# AVR.net
KiCad netlist of a schematic drawn in Altium Designer
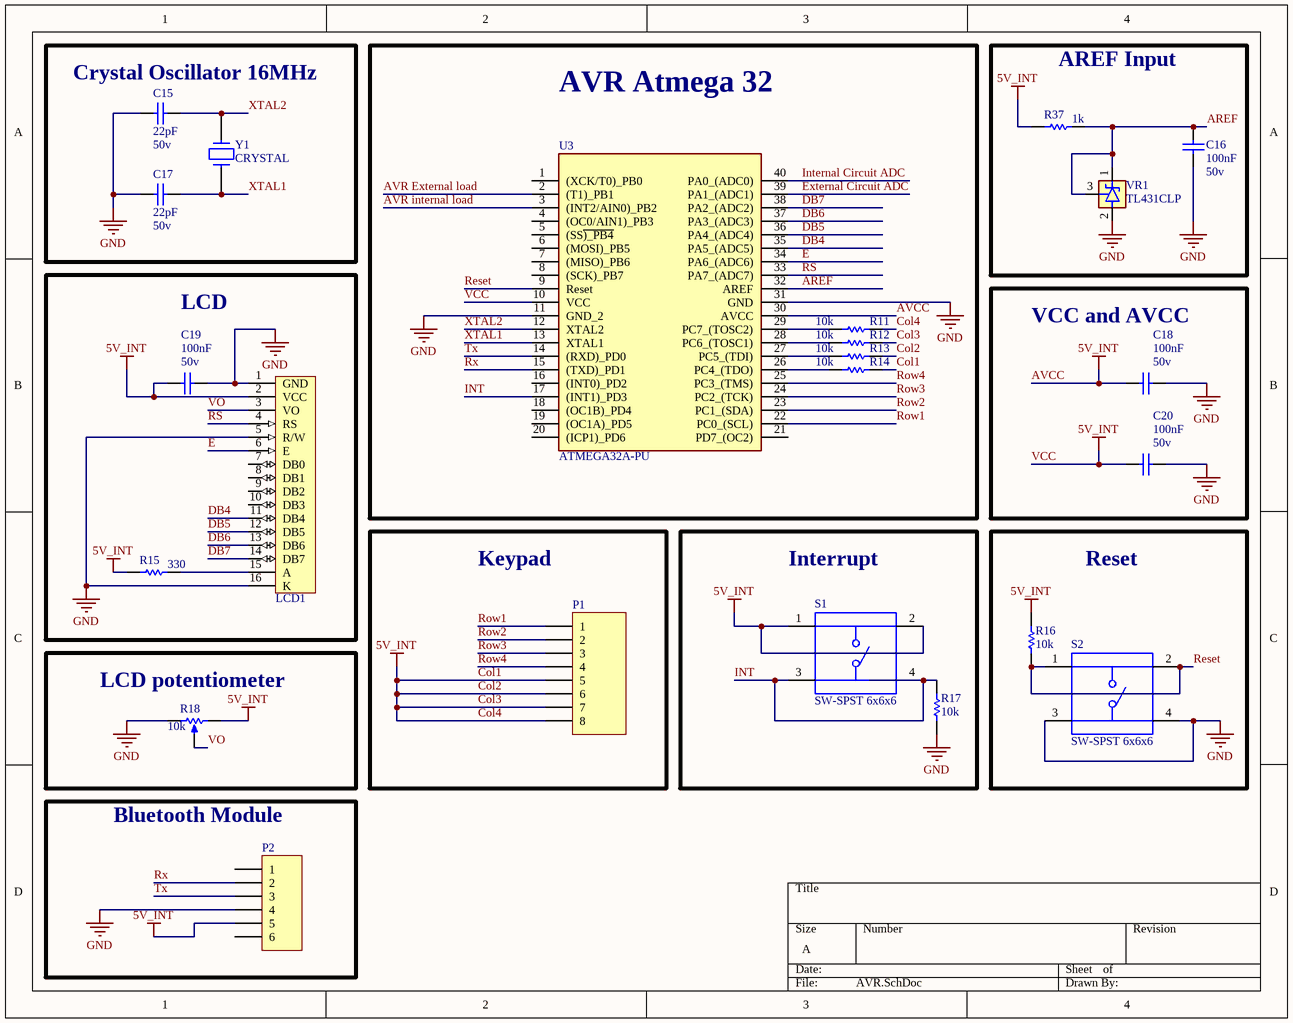
[diagram p0: AVR.SchDoc]

(export (version "E")
  (design (tool "Eeschema 10.0.6"))
  (components
    (comp (ref "C15")
      (value "22pF")
      (footprint "C0805")
      (description "None polar capacitor")
      (fields (field (name "ASID PART NUMBER") "C-AS") (field (name "VOLTE") "50v"))
      (libsource (lib "Mylib+Rev+4") (part "Cap ceramic"))
    )
    (comp (ref "C16")
      (value "100nF")
      (footprint "C0805")
      (description "None polar capacitor")
      (fields (field (name "ASID PART NUMBER") "C-AS") (field (name "VOLTE") "50v"))
      (libsource (lib "Mylib+Rev+4") (part "Cap ceramic"))
    )
    (comp (ref "C17")
      (value "22pF")
      (footprint "C0805")
      (description "None polar capacitor")
      (fields (field (name "ASID PART NUMBER") "C-AS") (field (name "VOLTE") "50v"))
      (libsource (lib "Mylib+Rev+4") (part "Cap ceramic"))
    )
    (comp (ref "C18")
      (value "100nF")
      (footprint "C0805")
      (description "None polar capacitor")
      (fields (field (name "ASID PART NUMBER") "C-AS") (field (name "VOLTE") "50v"))
      (libsource (lib "Mylib+Rev+4") (part "Cap ceramic"))
    )
    (comp (ref "C19")
      (value "100nF")
      (footprint "C0805")
      (description "None polar capacitor")
      (fields (field (name "ASID PART NUMBER") "C-AS") (field (name "VOLTE") "50v"))
      (libsource (lib "Mylib+Rev+4") (part "Cap ceramic"))
    )
    (comp (ref "C20")
      (value "100nF")
      (footprint "C0805")
      (description "None polar capacitor")
      (fields (field (name "ASID PART NUMBER") "C-AS") (field (name "VOLTE") "50v"))
      (libsource (lib "Mylib+Rev+4") (part "Cap ceramic"))
    )
    (comp (ref "LCD1")
      (value "LCD 16X2")
      (footprint "My_LCD 16x2-A")
      (description "LCD 16X2 Character lcd")
      (fields (field (name "ASID PART NUMBER") "LCD 16X2-AS"))
      (libsource (lib "Mylib+Rev+4") (part "LCD 16X2"))
    )
    (comp (ref "P1")
      (value "Header 8")
      (footprint "MY_1X08")
      (description "Header, 8-Pin, Dual row")
      (fields (field (name "ASID PART NUMBER") "Header 8-AS"))
      (libsource (lib "Mylib+Rev+4") (part "Header 8"))
    )
    (comp (ref "P2")
      (value "Header 6")
      (footprint "MY_FE06")
      (description "Header, 6-Pin")
      (fields (field (name "ASID PART NUMBER") "Header 6-AS"))
      (libsource (lib "Mylib+Rev+4") (part "Header 6"))
    )
    (comp (ref "R11")
      (value "10k")
      (footprint "R0603")
      (description "Standard resistor")
      (fields (field (name "ASID PART NUMBER") "Res-AS"))
      (libsource (lib "Mylib+Rev+4") (part "Res"))
    )
    (comp (ref "R12")
      (value "10k")
      (footprint "R0603")
      (description "Standard resistor")
      (fields (field (name "ASID PART NUMBER") "Res-AS"))
      (libsource (lib "Mylib+Rev+4") (part "Res"))
    )
    (comp (ref "R13")
      (value "10k")
      (footprint "R0603")
      (description "Standard resistor")
      (fields (field (name "ASID PART NUMBER") "Res-AS"))
      (libsource (lib "Mylib+Rev+4") (part "Res"))
    )
    (comp (ref "R14")
      (value "10k")
      (footprint "R0603")
      (description "Standard resistor")
      (fields (field (name "ASID PART NUMBER") "Res-AS"))
      (libsource (lib "Mylib+Rev+4") (part "Res"))
    )
    (comp (ref "R15")
      (value "330")
      (footprint "MY_(0.25w)_0207_10")
      (description "Standard resistor")
      (fields (field (name "ASID PART NUMBER") "Res-AS"))
      (libsource (lib "Mylib+Rev+4") (part "Res"))
    )
    (comp (ref "R16")
      (value "10k")
      (footprint "R0603")
      (description "Standard resistor")
      (fields (field (name "ASID PART NUMBER") "Res-AS"))
      (libsource (lib "Mylib+Rev+4") (part "Res"))
    )
    (comp (ref "R17")
      (value "10k")
      (footprint "R0603")
      (description "Standard resistor")
      (fields (field (name "ASID PART NUMBER") "Res-AS"))
      (libsource (lib "Mylib+Rev+4") (part "Res"))
    )
    (comp (ref "R18")
      (value "10k")
      (footprint "MY_TRIM3296W")
      (description "Potentiometer")
      (fields (field (name "ASID PART NUMBER") "Variable Resistor-AS"))
      (libsource (lib "Mylib+Rev+4") (part "Variable Resistor"))
    )
    (comp (ref "R37")
      (value "1k")
      (footprint "R0603")
      (description "Standard resistor")
      (fields (field (name "ASID PART NUMBER") "Res-AS"))
      (libsource (lib "Mylib+Rev+4") (part "Res"))
    )
    (comp (ref "S1")
      (value "SW-SPST 6x6x6")
      (footprint "SW-SPST 6x6x6")
      (description "6 x 6 mm, 6 mm Actuator Height, 160 gf, Black, Long Crimped, Through Hole, SPST, Tactile Switch")
      (fields (field (name "MF") "CUI Devices") (field (name "MP") "TS02-66-60-BK-160-LCR-D"))
      (libsource (lib "Miscellaneous Devices") (part "SW-SPST 6x6x6"))
    )
    (comp (ref "S2")
      (value "SW-SPST 6x6x6")
      (footprint "SW-SPST 6x6x6")
      (description "6 x 6 mm, 6 mm Actuator Height, 160 gf, Black, Long Crimped, Through Hole, SPST, Tactile Switch")
      (fields (field (name "MF") "CUI Devices") (field (name "MP") "TS02-66-60-BK-160-LCR-D"))
      (libsource (lib "Miscellaneous Devices") (part "SW-SPST 6x6x6"))
    )
    (comp (ref "U3")
      (value "ATMEGA32A-PU")
      (footprint "DIP40")
      (description "AVR AVR ATmega Microcontroller IC 8-Bit 16MHz 32KB (16K x 16) FLASH 40-PDIP")
      (fields (field (name "MF") "Microchip"))
      (libsource (lib "Mylib+Rev+4") (part "ATMEGA32A-PU"))
    )
    (comp (ref "VR1")
      (value "TL431CLP")
      (footprint "TO-92")
      (description "Adjustable precision shunt regulator")
      (fields (field (name "MF") "Texas Instruments"))
      (libsource (lib "Mylib+Rev+4") (part "TL431CLP"))
    )
    (comp (ref "Y1")
      (value "CRYSTAL")
      (footprint "My_Crystal")
      (description "Crystal")
      (fields (field (name "ASID PART NUMBER") "Crystal-AS"))
      (libsource (lib "Mylib+Rev+4") (part "CRYSTAL"))
    )
  )
  (nets
    (net (code "1") (name "/AREF") (class "Default")
      (node (ref "C16") (pin "1") (pinfunction "1_1") (pintype "passive"))
      (node (ref "R37") (pin "2") (pinfunction "2_2") (pintype "passive"))
      (node (ref "U3") (pin "32") (pinfunction "AREF_32") (pintype "passive"))
      (node (ref "VR1") (pin "1") (pinfunction "CATHODE_1") (pintype "passive"))
      (node (ref "VR1") (pin "3") (pinfunction "REF_3") (pintype "passive"))
    )
    (net (code "2") (name "/AVR External load") (class "Default")
      (node (ref "U3") (pin "2") (pinfunction "(T1)_PB1_2") (pintype "passive"))
    )
    (net (code "3") (name "/AVR internal load") (class "Default")
      (node (ref "U3") (pin "3") (pinfunction "(INT2/AIN0)_PB2_3") (pintype "passive"))
    )
    (net (code "4") (name "/DB4") (class "Default")
      (node (ref "LCD1") (pin "11") (pinfunction "DB4_11") (pintype "bidirectional"))
      (node (ref "U3") (pin "35") (pinfunction "PA5_(ADC5)_35") (pintype "passive"))
    )
    (net (code "5") (name "/DB5") (class "Default")
      (node (ref "LCD1") (pin "12") (pinfunction "DB5_12") (pintype "bidirectional"))
      (node (ref "U3") (pin "36") (pinfunction "PA4_(ADC4)_36") (pintype "passive"))
    )
    (net (code "6") (name "/DB6") (class "Default")
      (node (ref "LCD1") (pin "13") (pinfunction "DB6_13") (pintype "bidirectional"))
      (node (ref "U3") (pin "37") (pinfunction "PA3_(ADC3)_37") (pintype "passive"))
    )
    (net (code "7") (name "/DB7") (class "Default")
      (node (ref "LCD1") (pin "14") (pinfunction "DB7_14") (pintype "bidirectional"))
      (node (ref "U3") (pin "38") (pinfunction "PA2_(ADC2)_38") (pintype "passive"))
    )
    (net (code "8") (name "/E") (class "Default")
      (node (ref "LCD1") (pin "6") (pinfunction "E_6") (pintype "input"))
      (node (ref "U3") (pin "34") (pinfunction "PA6_(ADC6)_34") (pintype "passive"))
    )
    (net (code "9") (name "/External Circuit ADC") (class "Default")
      (node (ref "U3") (pin "39") (pinfunction "PA1_(ADC1)_39") (pintype "passive"))
    )
    (net (code "10") (name "/INT") (class "Default")
      (node (ref "R17") (pin "1") (pinfunction "1_1") (pintype "passive"))
      (node (ref "S1") (pin "3") (pinfunction "3_3") (pintype "passive"))
      (node (ref "S1") (pin "4") (pinfunction "4_4") (pintype "passive"))
      (node (ref "U3") (pin "17") (pinfunction "(INT1)_PD3_17") (pintype "passive"))
    )
    (net (code "11") (name "/Internal Circuit ADC") (class "Default")
      (node (ref "U3") (pin "40") (pinfunction "PA0_(ADC0)_40") (pintype "passive"))
    )
    (net (code "12") (name "/RS") (class "Default")
      (node (ref "LCD1") (pin "4") (pinfunction "RS_4") (pintype "input"))
      (node (ref "U3") (pin "33") (pinfunction "PA7_(ADC7)_33") (pintype "passive"))
    )
    (net (code "13") (name "/Reset") (class "Default")
      (node (ref "R16") (pin "2") (pinfunction "2_2") (pintype "passive"))
      (node (ref "S2") (pin "1") (pinfunction "1_1") (pintype "passive"))
      (node (ref "S2") (pin "2") (pinfunction "2_2") (pintype "passive"))
      (node (ref "U3") (pin "9") (pinfunction "Reset_9") (pintype "passive"))
    )
    (net (code "14") (name "/Row1") (class "Default")
      (node (ref "P1") (pin "1") (pinfunction "1_1") (pintype "passive"))
      (node (ref "U3") (pin "22") (pinfunction "PC0_(SCL)_22") (pintype "passive"))
    )
    (net (code "15") (name "/Row2") (class "Default")
      (node (ref "P1") (pin "2") (pinfunction "2_2") (pintype "passive"))
      (node (ref "U3") (pin "23") (pinfunction "PC1_(SDA)_23") (pintype "passive"))
    )
    (net (code "16") (name "/Row3") (class "Default")
      (node (ref "P1") (pin "3") (pinfunction "3_3") (pintype "passive"))
      (node (ref "U3") (pin "24") (pinfunction "PC2_(TCK)_24") (pintype "passive"))
    )
    (net (code "17") (name "/Row4") (class "Default")
      (node (ref "P1") (pin "4") (pinfunction "4_4") (pintype "passive"))
      (node (ref "U3") (pin "25") (pinfunction "PC3_(TMS)_25") (pintype "passive"))
    )
    (net (code "18") (name "/Rx") (class "Default")
      (node (ref "P2") (pin "2") (pinfunction "2_2") (pintype "passive"))
      (node (ref "U3") (pin "15") (pinfunction "(TXD)_PD1_15") (pintype "passive"))
    )
    (net (code "19") (name "/Tx") (class "Default")
      (node (ref "P2") (pin "3") (pinfunction "3_3") (pintype "passive"))
      (node (ref "U3") (pin "14") (pinfunction "(RXD)_PD0_14") (pintype "passive"))
    )
    (net (code "20") (name "/VO") (class "Default")
      (node (ref "LCD1") (pin "3") (pinfunction "VO_3") (pintype "passive"))
      (node (ref "R18") (pin "3") (pinfunction "TAP_3") (pintype "passive"))
    )
    (net (code "21") (name "/XTAL1") (class "Default")
      (node (ref "C17") (pin "2") (pinfunction "2_2") (pintype "passive"))
      (node (ref "U3") (pin "13") (pinfunction "XTAL1_13") (pintype "passive"))
      (node (ref "Y1") (pin "1") (pinfunction "1_1") (pintype "passive"))
    )
    (net (code "22") (name "/XTAL2") (class "Default")
      (node (ref "C15") (pin "2") (pinfunction "2_2") (pintype "passive"))
      (node (ref "U3") (pin "12") (pinfunction "XTAL2_12") (pintype "passive"))
      (node (ref "Y1") (pin "2") (pinfunction "2_2") (pintype "passive"))
    )
    (net (code "23") (name "5V_INT") (class "Default")
      (node (ref "C18") (pin "2") (pinfunction "2_2") (pintype "passive"))
      (node (ref "C19") (pin "2") (pinfunction "2_2") (pintype "passive"))
      (node (ref "C20") (pin "2") (pinfunction "2_2") (pintype "passive"))
      (node (ref "LCD1") (pin "2") (pinfunction "VCC_2") (pintype "power_in"))
      (node (ref "P1") (pin "5") (pinfunction "5_5") (pintype "passive"))
      (node (ref "P1") (pin "6") (pinfunction "6_6") (pintype "passive"))
      (node (ref "P1") (pin "7") (pinfunction "7_7") (pintype "passive"))
      (node (ref "P1") (pin "8") (pinfunction "8_8") (pintype "passive"))
      (node (ref "P2") (pin "5") (pinfunction "5_5") (pintype "passive"))
      (node (ref "R11") (pin "2") (pinfunction "2_2") (pintype "passive"))
      (node (ref "R12") (pin "2") (pinfunction "2_2") (pintype "passive"))
      (node (ref "R13") (pin "2") (pinfunction "2_2") (pintype "passive"))
      (node (ref "R14") (pin "2") (pinfunction "2_2") (pintype "passive"))
      (node (ref "R15") (pin "1") (pinfunction "1_1") (pintype "passive"))
      (node (ref "R16") (pin "1") (pinfunction "1_1") (pintype "passive"))
      (node (ref "R18") (pin "2") (pinfunction "BOT_2") (pintype "passive"))
      (node (ref "R37") (pin "1") (pinfunction "1_1") (pintype "passive"))
      (node (ref "S1") (pin "1") (pinfunction "1_1") (pintype "passive"))
      (node (ref "S1") (pin "2") (pinfunction "2_2") (pintype "passive"))
      (node (ref "U3") (pin "10") (pinfunction "VCC_10") (pintype "passive"))
      (node (ref "U3") (pin "30") (pinfunction "AVCC_30") (pintype "passive"))
    )
    (net (code "24") (name "GND") (class "Default")
      (node (ref "C15") (pin "1") (pinfunction "1_1") (pintype "passive"))
      (node (ref "C16") (pin "2") (pinfunction "2_2") (pintype "passive"))
      (node (ref "C17") (pin "1") (pinfunction "1_1") (pintype "passive"))
      (node (ref "C18") (pin "1") (pinfunction "1_1") (pintype "passive"))
      (node (ref "C19") (pin "1") (pinfunction "1_1") (pintype "passive"))
      (node (ref "C20") (pin "1") (pinfunction "1_1") (pintype "passive"))
      (node (ref "LCD1") (pin "1") (pinfunction "GND_1") (pintype "power_in"))
      (node (ref "LCD1") (pin "16") (pinfunction "K_16") (pintype "passive"))
      (node (ref "LCD1") (pin "5") (pinfunction "R/W_5") (pintype "input"))
      (node (ref "P2") (pin "4") (pinfunction "4_4") (pintype "passive"))
      (node (ref "R17") (pin "2") (pinfunction "2_2") (pintype "passive"))
      (node (ref "R18") (pin "1") (pinfunction "TOP_1") (pintype "passive"))
      (node (ref "S2") (pin "3") (pinfunction "3_3") (pintype "passive"))
      (node (ref "S2") (pin "4") (pinfunction "4_4") (pintype "passive"))
      (node (ref "U3") (pin "11") (pinfunction "GND_2_11") (pintype "passive"))
      (node (ref "U3") (pin "31") (pinfunction "GND_31") (pintype "passive"))
      (node (ref "VR1") (pin "2") (pinfunction "ANODE_2") (pintype "passive"))
    )
    (net (code "25") (name "Net-(LCD1-A)") (class "Default")
      (node (ref "LCD1") (pin "15") (pinfunction "A_15") (pintype "passive"))
      (node (ref "R15") (pin "2") (pinfunction "2_2") (pintype "passive"))
    )
    (net (code "26") (name "Net-(U3-PC4_(TDO))") (class "Default")
      (node (ref "R14") (pin "1") (pinfunction "1_1") (pintype "passive"))
      (node (ref "U3") (pin "26") (pinfunction "PC4_(TDO)_26") (pintype "passive"))
    )
    (net (code "27") (name "Net-(U3-PC5_(TDI))") (class "Default")
      (node (ref "R13") (pin "1") (pinfunction "1_1") (pintype "passive"))
      (node (ref "U3") (pin "27") (pinfunction "PC5_(TDI)_27") (pintype "passive"))
    )
    (net (code "28") (name "Net-(U3-PC6_(TOSC1))") (class "Default")
      (node (ref "R12") (pin "1") (pinfunction "1_1") (pintype "passive"))
      (node (ref "U3") (pin "28") (pinfunction "PC6_(TOSC1)_28") (pintype "passive"))
    )
    (net (code "29") (name "Net-(U3-PC7_(TOSC2))") (class "Default")
      (node (ref "R11") (pin "1") (pinfunction "1_1") (pintype "passive"))
      (node (ref "U3") (pin "29") (pinfunction "PC7_(TOSC2)_29") (pintype "passive"))
    )
    (net (code "30") (name "unconnected-(LCD1-DB0-Pad7)") (class "Default")
      (node (ref "LCD1") (pin "7") (pinfunction "DB0_7") (pintype "bidirectional"))
    )
    (net (code "31") (name "unconnected-(LCD1-DB1-Pad8)") (class "Default")
      (node (ref "LCD1") (pin "8") (pinfunction "DB1_8") (pintype "bidirectional"))
    )
    (net (code "32") (name "unconnected-(LCD1-DB2-Pad9)") (class "Default")
      (node (ref "LCD1") (pin "9") (pinfunction "DB2_9") (pintype "bidirectional"))
    )
    (net (code "33") (name "unconnected-(LCD1-DB3-Pad10)") (class "Default")
      (node (ref "LCD1") (pin "10") (pinfunction "DB3_10") (pintype "bidirectional"))
    )
    (net (code "34") (name "unconnected-(P2-Pad1)") (class "Default")
      (node (ref "P2") (pin "1") (pinfunction "1_1") (pintype "passive"))
    )
    (net (code "35") (name "unconnected-(P2-Pad6)") (class "Default")
      (node (ref "P2") (pin "6") (pinfunction "6_6") (pintype "passive"))
    )
    (net (code "36") (name "unconnected-(U3-(ICP1)_PD6-Pad20)") (class "Default")
      (node (ref "U3") (pin "20") (pinfunction "(ICP1)_PD6_20") (pintype "passive"))
    )
    (net (code "37") (name "unconnected-(U3-(INT0)_PD2-Pad16)") (class "Default")
      (node (ref "U3") (pin "16") (pinfunction "(INT0)_PD2_16") (pintype "passive"))
    )
    (net (code "38") (name "unconnected-(U3-(MISO)_PB6-Pad7)") (class "Default")
      (node (ref "U3") (pin "7") (pinfunction "(MISO)_PB6_7") (pintype "passive"))
    )
    (net (code "39") (name "unconnected-(U3-(MOSI)_PB5-Pad6)") (class "Default")
      (node (ref "U3") (pin "6") (pinfunction "(MOSI)_PB5_6") (pintype "passive"))
    )
    (net (code "40") (name "unconnected-(U3-(OC0{slash}AIN1)_PB3-Pad4)") (class "Default")
      (node (ref "U3") (pin "4") (pinfunction "(OC0/AIN1)_PB3_4") (pintype "passive"))
    )
    (net (code "41") (name "unconnected-(U3-(OC1A)_PD5-Pad19)") (class "Default")
      (node (ref "U3") (pin "19") (pinfunction "(OC1A)_PD5_19") (pintype "passive"))
    )
    (net (code "42") (name "unconnected-(U3-(OC1B)_PD4-Pad18)") (class "Default")
      (node (ref "U3") (pin "18") (pinfunction "(OC1B)_PD4_18") (pintype "passive"))
    )
    (net (code "43") (name "unconnected-(U3-(SCK)_PB7-Pad8)") (class "Default")
      (node (ref "U3") (pin "8") (pinfunction "(SCK)_PB7_8") (pintype "passive"))
    )
    (net (code "44") (name "unconnected-(U3-(SS~{)_PB4}-Pad5)") (class "Default")
      (node (ref "U3") (pin "5") (pinfunction "(SS~{)_PB4}_5") (pintype "passive"))
    )
    (net (code "45") (name "unconnected-(U3-(XCK{slash}T0)_PB0-Pad1)") (class "Default")
      (node (ref "U3") (pin "1") (pinfunction "(XCK/T0)_PB0_1") (pintype "passive"))
    )
    (net (code "46") (name "unconnected-(U3-PD7_(OC2)-Pad21)") (class "Default")
      (node (ref "U3") (pin "21") (pinfunction "PD7_(OC2)_21") (pintype "passive"))
    )
  )
)
